# MCU_IO.net
KiCad netlist of a schematic drawn in Altium Designer
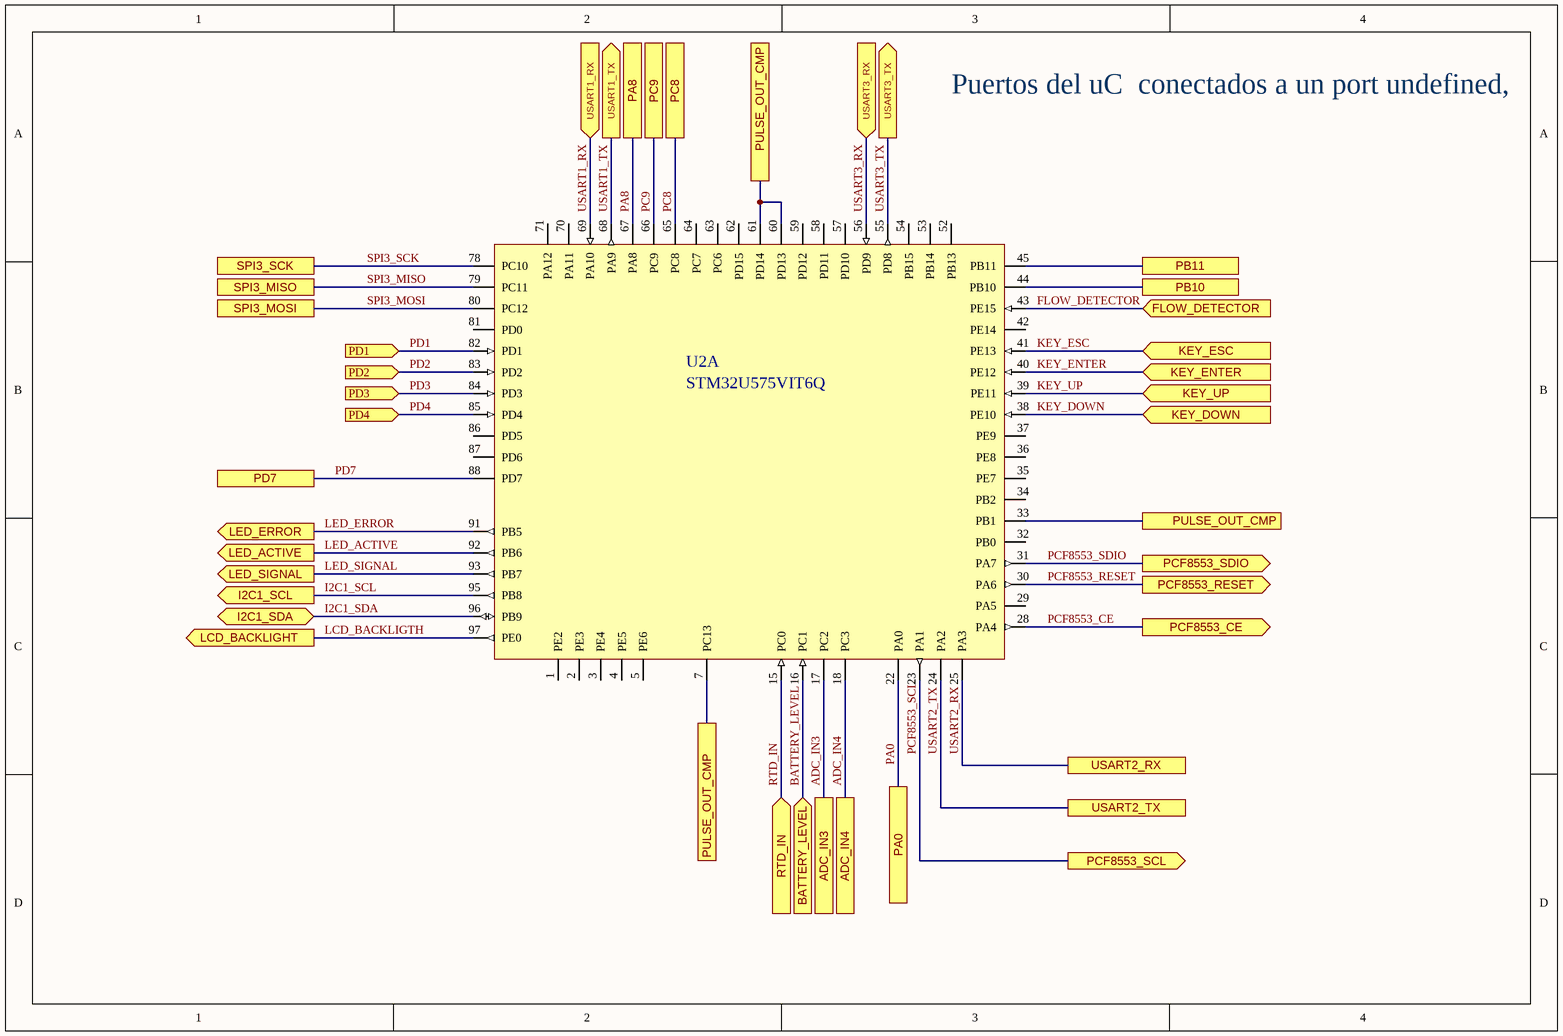
[diagram p0: MCU_IO.SchDoc]

(export (version "E")
  (design (tool "Eeschema 10.0.6"))
  (components
    (comp (ref "U2")
      (value "STM32U575VIT6Q")
      (footprint "STM32U575VI")
      (fields (field (name "MANUFACTURER") "ST"))
      (libsource (lib "Microcontroladores") (part "STM32U575VI_1"))
    )
  )
  (nets
    (net (code "1") (name "/ADC_IN3") (class "Default")
      (node (ref "U2") (pin "17") (pinfunction "PC2_17") (pintype "tri_state"))
    )
    (net (code "2") (name "/ADC_IN4") (class "Default")
      (node (ref "U2") (pin "18") (pinfunction "PC3_18") (pintype "tri_state"))
    )
    (net (code "3") (name "/BATTERY_LEVEL") (class "Default")
      (node (ref "U2") (pin "16") (pinfunction "PC1_16") (pintype "input"))
    )
    (net (code "4") (name "/FLOW_DETECTOR") (class "Default")
      (node (ref "U2") (pin "43") (pinfunction "PE15_43") (pintype "input"))
    )
    (net (code "5") (name "/I2C1_SCL") (class "Default")
      (node (ref "U2") (pin "95") (pinfunction "PB8_95") (pintype "output"))
    )
    (net (code "6") (name "/I2C1_SDA") (class "Default")
      (node (ref "U2") (pin "96") (pinfunction "PB9_96") (pintype "bidirectional"))
    )
    (net (code "7") (name "/KEY_DOWN") (class "Default")
      (node (ref "U2") (pin "38") (pinfunction "PE10_38") (pintype "input"))
    )
    (net (code "8") (name "/KEY_ENTER") (class "Default")
      (node (ref "U2") (pin "40") (pinfunction "PE12_40") (pintype "input"))
    )
    (net (code "9") (name "/KEY_ESC") (class "Default")
      (node (ref "U2") (pin "41") (pinfunction "PE13_41") (pintype "input"))
    )
    (net (code "10") (name "/KEY_UP") (class "Default")
      (node (ref "U2") (pin "39") (pinfunction "PE11_39") (pintype "input"))
    )
    (net (code "11") (name "/LCD_BACKLIGTH") (class "Default")
      (node (ref "U2") (pin "97") (pinfunction "PE0_97") (pintype "output"))
    )
    (net (code "12") (name "/LED_ACTIVE") (class "Default")
      (node (ref "U2") (pin "92") (pinfunction "PB6_92") (pintype "output"))
    )
    (net (code "13") (name "/LED_ERROR") (class "Default")
      (node (ref "U2") (pin "91") (pinfunction "PB5_91") (pintype "output"))
    )
    (net (code "14") (name "/LED_SIGNAL") (class "Default")
      (node (ref "U2") (pin "93") (pinfunction "PB7_93") (pintype "output"))
    )
    (net (code "15") (name "/PA0") (class "Default")
      (node (ref "U2") (pin "22") (pinfunction "PA0_22") (pintype "tri_state"))
    )
    (net (code "16") (name "/PA8") (class "Default")
      (node (ref "U2") (pin "67") (pinfunction "PA8_67") (pintype "tri_state"))
    )
    (net (code "17") (name "/PB10") (class "Default")
      (node (ref "U2") (pin "44") (pinfunction "PB10_44") (pintype "tri_state"))
    )
    (net (code "18") (name "/PB11") (class "Default")
      (node (ref "U2") (pin "45") (pinfunction "PB11_45") (pintype "tri_state"))
    )
    (net (code "19") (name "/PC8") (class "Default")
      (node (ref "U2") (pin "65") (pinfunction "PC8_65") (pintype "tri_state"))
    )
    (net (code "20") (name "/PC9") (class "Default")
      (node (ref "U2") (pin "66") (pinfunction "PC9_66") (pintype "tri_state"))
    )
    (net (code "21") (name "/PCF8553_CE") (class "Default")
      (node (ref "U2") (pin "28") (pinfunction "PA4_28") (pintype "output"))
    )
    (net (code "22") (name "/PCF8553_RESET") (class "Default")
      (node (ref "U2") (pin "30") (pinfunction "PA6_30") (pintype "output"))
    )
    (net (code "23") (name "/PCF8553_SCL") (class "Default")
      (node (ref "U2") (pin "23") (pinfunction "PA1_23") (pintype "output"))
    )
    (net (code "24") (name "/PCF8553_SDIO") (class "Default")
      (node (ref "U2") (pin "31") (pinfunction "PA7_31") (pintype "output"))
    )
    (net (code "25") (name "/PD1") (class "Default")
      (node (ref "U2") (pin "82") (pinfunction "PD1_82") (pintype "input"))
    )
    (net (code "26") (name "/PD2") (class "Default")
      (node (ref "U2") (pin "83") (pinfunction "PD2_83") (pintype "input"))
    )
    (net (code "27") (name "/PD3") (class "Default")
      (node (ref "U2") (pin "84") (pinfunction "PD3_84") (pintype "input"))
    )
    (net (code "28") (name "/PD4") (class "Default")
      (node (ref "U2") (pin "85") (pinfunction "PD4_85") (pintype "input"))
    )
    (net (code "29") (name "/PD7") (class "Default")
      (node (ref "U2") (pin "88") (pinfunction "PD7_88") (pintype "tri_state"))
    )
    (net (code "30") (name "/PULSE_OUT_CMP") (class "Default")
      (node (ref "U2") (pin "33") (pinfunction "PB1_33") (pintype "tri_state"))
      (node (ref "U2") (pin "60") (pinfunction "PD13_60") (pintype "passive"))
      (node (ref "U2") (pin "61") (pinfunction "PD14_61") (pintype "passive"))
      (node (ref "U2") (pin "7") (pinfunction "PC13_7") (pintype "passive"))
    )
    (net (code "31") (name "/RTD_IN") (class "Default")
      (node (ref "U2") (pin "15") (pinfunction "PC0_15") (pintype "input"))
    )
    (net (code "32") (name "/SPI3_MISO") (class "Default")
      (node (ref "U2") (pin "79") (pinfunction "PC11_79") (pintype "tri_state"))
    )
    (net (code "33") (name "/SPI3_MOSI") (class "Default")
      (node (ref "U2") (pin "80") (pinfunction "PC12_80") (pintype "tri_state"))
    )
    (net (code "34") (name "/SPI3_SCK") (class "Default")
      (node (ref "U2") (pin "78") (pinfunction "PC10_78") (pintype "tri_state"))
    )
    (net (code "35") (name "/USART1_RX") (class "Default")
      (node (ref "U2") (pin "69") (pinfunction "PA10_69") (pintype "input"))
    )
    (net (code "36") (name "/USART1_TX") (class "Default")
      (node (ref "U2") (pin "68") (pinfunction "PA9_68") (pintype "output"))
    )
    (net (code "37") (name "/USART2_RX") (class "Default")
      (node (ref "U2") (pin "25") (pinfunction "PA3_25") (pintype "tri_state"))
    )
    (net (code "38") (name "/USART2_TX") (class "Default")
      (node (ref "U2") (pin "24") (pinfunction "PA2_24") (pintype "tri_state"))
    )
    (net (code "39") (name "/USART3_RX") (class "Default")
      (node (ref "U2") (pin "56") (pinfunction "PD9_56") (pintype "input"))
    )
    (net (code "40") (name "/USART3_TX") (class "Default")
      (node (ref "U2") (pin "55") (pinfunction "PD8_55") (pintype "output"))
    )
    (net (code "41") (name "unconnected-(U2A-PA5-Pad29)") (class "Default")
      (node (ref "U2") (pin "29") (pinfunction "PA5_29") (pintype "tri_state"))
    )
    (net (code "42") (name "unconnected-(U2A-PA11-Pad70)") (class "Default")
      (node (ref "U2") (pin "70") (pinfunction "PA11_70") (pintype "tri_state"))
    )
    (net (code "43") (name "unconnected-(U2A-PA12-Pad71)") (class "Default")
      (node (ref "U2") (pin "71") (pinfunction "PA12_71") (pintype "tri_state"))
    )
    (net (code "44") (name "unconnected-(U2A-PB0-Pad32)") (class "Default")
      (node (ref "U2") (pin "32") (pinfunction "PB0_32") (pintype "tri_state"))
    )
    (net (code "45") (name "unconnected-(U2A-PB2-Pad34)") (class "Default")
      (node (ref "U2") (pin "34") (pinfunction "PB2_34") (pintype "tri_state"))
    )
    (net (code "46") (name "unconnected-(U2A-PB13-Pad52)") (class "Default")
      (node (ref "U2") (pin "52") (pinfunction "PB13_52") (pintype "tri_state"))
    )
    (net (code "47") (name "unconnected-(U2A-PB14-Pad53)") (class "Default")
      (node (ref "U2") (pin "53") (pinfunction "PB14_53") (pintype "tri_state"))
    )
    (net (code "48") (name "unconnected-(U2A-PB15-Pad54)") (class "Default")
      (node (ref "U2") (pin "54") (pinfunction "PB15_54") (pintype "tri_state"))
    )
    (net (code "49") (name "unconnected-(U2A-PC6-Pad63)") (class "Default")
      (node (ref "U2") (pin "63") (pinfunction "PC6_63") (pintype "tri_state"))
    )
    (net (code "50") (name "unconnected-(U2A-PC7-Pad64)") (class "Default")
      (node (ref "U2") (pin "64") (pinfunction "PC7_64") (pintype "tri_state"))
    )
    (net (code "51") (name "unconnected-(U2A-PD0-Pad81)") (class "Default")
      (node (ref "U2") (pin "81") (pinfunction "PD0_81") (pintype "tri_state"))
    )
    (net (code "52") (name "unconnected-(U2A-PD5-Pad86)") (class "Default")
      (node (ref "U2") (pin "86") (pinfunction "PD5_86") (pintype "tri_state"))
    )
    (net (code "53") (name "unconnected-(U2A-PD6-Pad87)") (class "Default")
      (node (ref "U2") (pin "87") (pinfunction "PD6_87") (pintype "tri_state"))
    )
    (net (code "54") (name "unconnected-(U2A-PD10-Pad57)") (class "Default")
      (node (ref "U2") (pin "57") (pinfunction "PD10_57") (pintype "tri_state"))
    )
    (net (code "55") (name "unconnected-(U2A-PD11-Pad58)") (class "Default")
      (node (ref "U2") (pin "58") (pinfunction "PD11_58") (pintype "tri_state"))
    )
    (net (code "56") (name "unconnected-(U2A-PD12-Pad59)") (class "Default")
      (node (ref "U2") (pin "59") (pinfunction "PD12_59") (pintype "tri_state"))
    )
    (net (code "57") (name "unconnected-(U2A-PD15-Pad62)") (class "Default")
      (node (ref "U2") (pin "62") (pinfunction "PD15_62") (pintype "tri_state"))
    )
    (net (code "58") (name "unconnected-(U2A-PE2-Pad1)") (class "Default")
      (node (ref "U2") (pin "1") (pinfunction "PE2_1") (pintype "tri_state"))
    )
    (net (code "59") (name "unconnected-(U2A-PE3-Pad2)") (class "Default")
      (node (ref "U2") (pin "2") (pinfunction "PE3_2") (pintype "tri_state"))
    )
    (net (code "60") (name "unconnected-(U2A-PE4-Pad3)") (class "Default")
      (node (ref "U2") (pin "3") (pinfunction "PE4_3") (pintype "tri_state"))
    )
    (net (code "61") (name "unconnected-(U2A-PE5-Pad4)") (class "Default")
      (node (ref "U2") (pin "4") (pinfunction "PE5_4") (pintype "tri_state"))
    )
    (net (code "62") (name "unconnected-(U2A-PE6-Pad5)") (class "Default")
      (node (ref "U2") (pin "5") (pinfunction "PE6_5") (pintype "tri_state"))
    )
    (net (code "63") (name "unconnected-(U2A-PE7-Pad35)") (class "Default")
      (node (ref "U2") (pin "35") (pinfunction "PE7_35") (pintype "tri_state"))
    )
    (net (code "64") (name "unconnected-(U2A-PE8-Pad36)") (class "Default")
      (node (ref "U2") (pin "36") (pinfunction "PE8_36") (pintype "tri_state"))
    )
    (net (code "65") (name "unconnected-(U2A-PE9-Pad37)") (class "Default")
      (node (ref "U2") (pin "37") (pinfunction "PE9_37") (pintype "tri_state"))
    )
    (net (code "66") (name "unconnected-(U2A-PE14-Pad42)") (class "Default")
      (node (ref "U2") (pin "42") (pinfunction "PE14_42") (pintype "tri_state"))
    )
  )
)
